# LCD16x2.net
KiCad netlist of a schematic drawn in Altium Designer
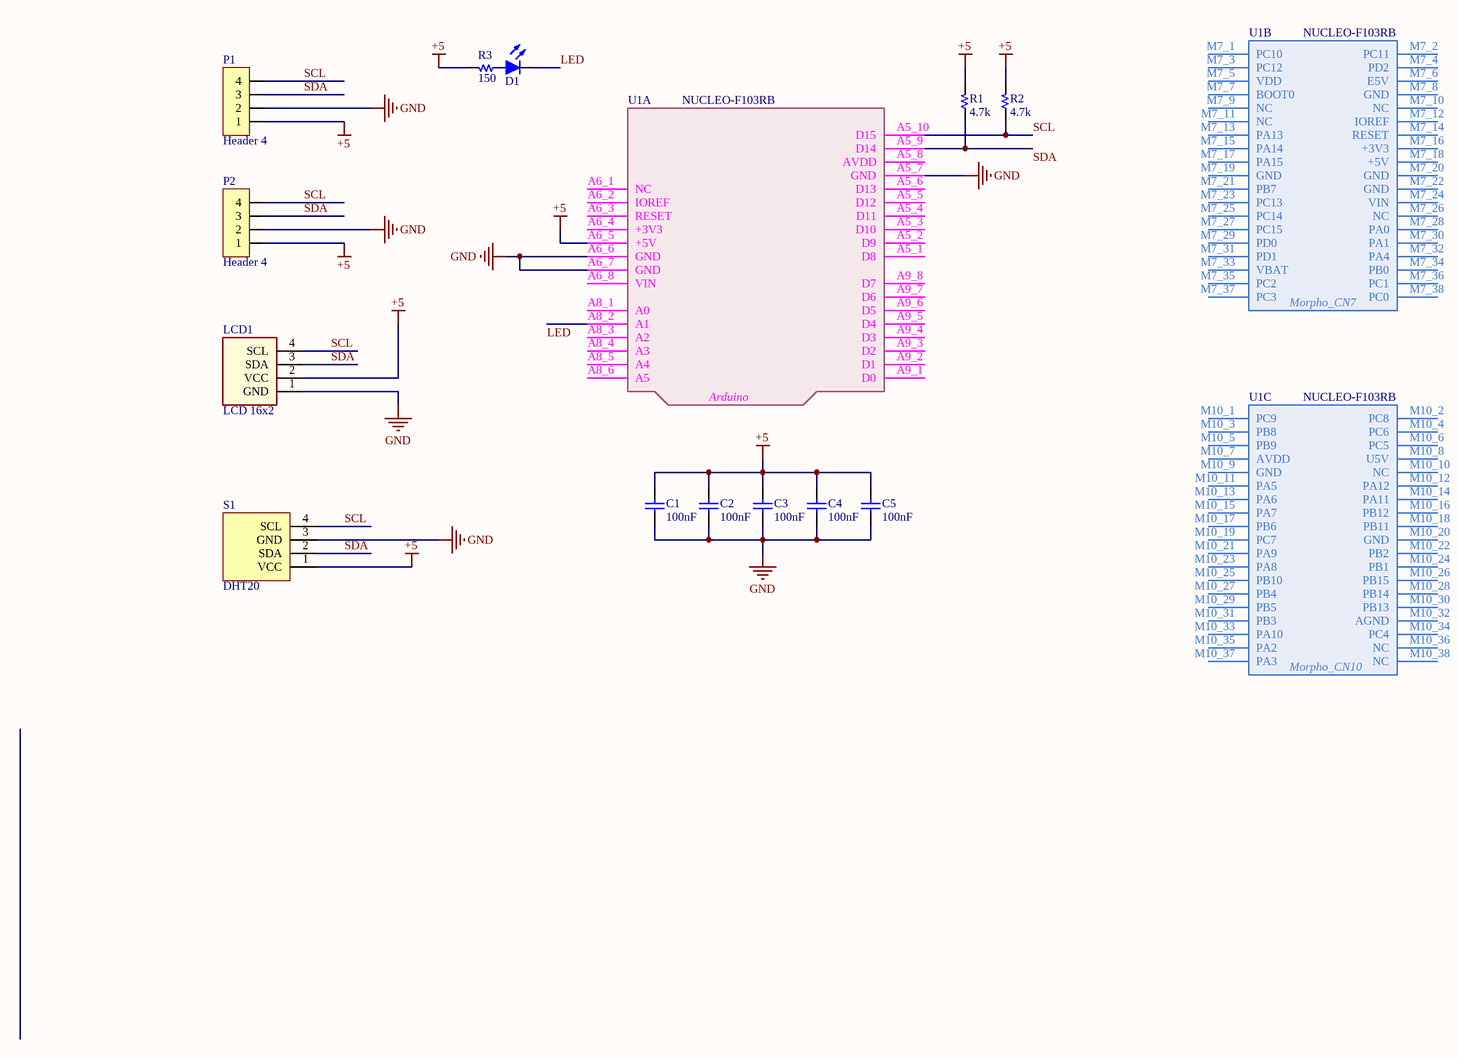
[diagram p0: LCD16x2.SchDoc]

(export (version "E")
  (design (tool "Eeschema 10.0.6"))
  (components
    (comp (ref "C1")
      (value "100nF")
      (footprint "C 0805")
      (description "Capacitor non-pol")
      (libsource (lib "chipfc_altium_libs") (part "Capacitor NP"))
    )
    (comp (ref "C2")
      (value "100nF")
      (footprint "C 0805")
      (description "Capacitor non-pol")
      (libsource (lib "chipfc_altium_libs") (part "Capacitor NP"))
    )
    (comp (ref "C3")
      (value "100nF")
      (footprint "C 0805")
      (description "Capacitor non-pol")
      (libsource (lib "chipfc_altium_libs") (part "Capacitor NP"))
    )
    (comp (ref "C4")
      (value "100nF")
      (footprint "C 0805")
      (description "Capacitor non-pol")
      (libsource (lib "chipfc_altium_libs") (part "Capacitor NP"))
    )
    (comp (ref "C5")
      (value "100nF")
      (footprint "C 0805")
      (description "Capacitor non-pol")
      (libsource (lib "chipfc_altium_libs") (part "Capacitor NP"))
    )
    (comp (ref "D1")
      (value "Led")
      (footprint "LED 3MM - red")
      (description "Typical LED")
      (libsource (lib "chipfc_altium_libs") (part "Led"))
    )
    (comp (ref "LCD1")
      (value "LCD 16x2")
      (footprint "LCD 1602A I2C")
      (description "Character LCD 16x2")
      (libsource (lib "bk2022") (part "LCD 16x2"))
    )
    (comp (ref "P1")
      (value "Header 4")
      (footprint "HDR/Header/4/BOX")
      (description "Header, 4-Pin")
      (libsource (lib "chipfc_altium_libs") (part "Header 4"))
    )
    (comp (ref "P2")
      (value "Header 4")
      (footprint "HDR/Header/4/BOX")
      (description "Header, 4-Pin")
      (libsource (lib "chipfc_altium_libs") (part "Header 4"))
    )
    (comp (ref "R1")
      (value "4.7k")
      (footprint "R 0805")
      (description "Resistor")
      (libsource (lib "chipfc_altium_libs") (part "Resistor"))
    )
    (comp (ref "R2")
      (value "4.7k")
      (footprint "R 0805")
      (description "Resistor")
      (libsource (lib "chipfc_altium_libs") (part "Resistor"))
    )
    (comp (ref "R3")
      (value "150")
      (footprint "R 0805")
      (description "Resistor")
      (libsource (lib "chipfc_altium_libs") (part "Resistor"))
    )
    (comp (ref "S1")
      (value "DHT20")
      (footprint "DTH20/H")
      (description "DTH20 Temperature and humidity module")
      (libsource (lib "chipfc_altium_libs") (part "DTH20"))
    )
    (comp (ref "U1")
      (value "NUCLEO-F103RB")
      (footprint "NUCLEO")
      (fields (field (name "MANUFACTURER") "STMicroelectronics"))
      (libsource (lib "nucleo") (part "NUCLEO-F103RB"))
    )
  )
  (nets
    (net (code "1") (name "+5") (class "Default")
      (node (ref "C1") (pin "1") (pinfunction "1_1") (pintype "passive"))
      (node (ref "C2") (pin "1") (pinfunction "1_1") (pintype "passive"))
      (node (ref "C3") (pin "1") (pinfunction "1_1") (pintype "passive"))
      (node (ref "C4") (pin "1") (pinfunction "1_1") (pintype "passive"))
      (node (ref "C5") (pin "1") (pinfunction "1_1") (pintype "passive"))
      (node (ref "LCD1") (pin "2") (pinfunction "VCC_2") (pintype "passive"))
      (node (ref "P1") (pin "1") (pinfunction "1_1") (pintype "passive"))
      (node (ref "P2") (pin "1") (pinfunction "1_1") (pintype "passive"))
      (node (ref "R1") (pin "2") (pinfunction "2_2") (pintype "passive"))
      (node (ref "R2") (pin "2") (pinfunction "2_2") (pintype "passive"))
      (node (ref "R3") (pin "2") (pinfunction "2_2") (pintype "passive"))
      (node (ref "S1") (pin "1") (pinfunction "VCC_1") (pintype "passive"))
      (node (ref "U1") (pin "A6_5") (pinfunction "+5V_A6_5") (pintype "passive"))
    )
    (net (code "2") (name "/LED") (class "Default")
      (node (ref "D1") (pin "2") (pinfunction "K_2") (pintype "passive"))
      (node (ref "U1") (pin "A8_2") (pinfunction "A1_A8_2") (pintype "passive"))
    )
    (net (code "3") (name "/SCL") (class "Default")
      (node (ref "LCD1") (pin "4") (pinfunction "SCL_4") (pintype "passive"))
      (node (ref "P1") (pin "4") (pinfunction "4_4") (pintype "passive"))
      (node (ref "P2") (pin "4") (pinfunction "4_4") (pintype "passive"))
      (node (ref "R2") (pin "1") (pinfunction "1_1") (pintype "passive"))
      (node (ref "S1") (pin "4") (pinfunction "SCL_4") (pintype "passive"))
      (node (ref "U1") (pin "A5_10") (pinfunction "D15_A5_10") (pintype "passive"))
    )
    (net (code "4") (name "/SDA") (class "Default")
      (node (ref "LCD1") (pin "3") (pinfunction "SDA_3") (pintype "passive"))
      (node (ref "P1") (pin "3") (pinfunction "3_3") (pintype "passive"))
      (node (ref "P2") (pin "3") (pinfunction "3_3") (pintype "passive"))
      (node (ref "R1") (pin "1") (pinfunction "1_1") (pintype "passive"))
      (node (ref "S1") (pin "2") (pinfunction "SDA_2") (pintype "passive"))
      (node (ref "U1") (pin "A5_9") (pinfunction "D14_A5_9") (pintype "passive"))
    )
    (net (code "5") (name "GND") (class "Default")
      (node (ref "C1") (pin "2") (pinfunction "2_2") (pintype "passive"))
      (node (ref "C2") (pin "2") (pinfunction "2_2") (pintype "passive"))
      (node (ref "C3") (pin "2") (pinfunction "2_2") (pintype "passive"))
      (node (ref "C4") (pin "2") (pinfunction "2_2") (pintype "passive"))
      (node (ref "C5") (pin "2") (pinfunction "2_2") (pintype "passive"))
      (node (ref "LCD1") (pin "1") (pinfunction "GND_1") (pintype "passive"))
      (node (ref "P1") (pin "2") (pinfunction "2_2") (pintype "passive"))
      (node (ref "P2") (pin "2") (pinfunction "2_2") (pintype "passive"))
      (node (ref "S1") (pin "3") (pinfunction "GND_3") (pintype "passive"))
      (node (ref "U1") (pin "A5_7") (pinfunction "GND_A5_7") (pintype "passive"))
      (node (ref "U1") (pin "A6_6") (pinfunction "GND_A6_6") (pintype "passive"))
      (node (ref "U1") (pin "A6_7") (pinfunction "GND_A6_7") (pintype "passive"))
    )
    (net (code "6") (name "Net-(D1-A)") (class "Default")
      (node (ref "D1") (pin "1") (pinfunction "A_1") (pintype "passive"))
      (node (ref "R3") (pin "1") (pinfunction "1_1") (pintype "passive"))
    )
    (net (code "7") (name "unconnected-(U1A-+3V3-PadA6_4)") (class "Default")
      (node (ref "U1") (pin "A6_4") (pinfunction "+3V3_A6_4") (pintype "passive"))
    )
    (net (code "8") (name "unconnected-(U1A-A0-PadA8_1)") (class "Default")
      (node (ref "U1") (pin "A8_1") (pinfunction "A0_A8_1") (pintype "passive"))
    )
    (net (code "9") (name "unconnected-(U1A-A2-PadA8_3)") (class "Default")
      (node (ref "U1") (pin "A8_3") (pinfunction "A2_A8_3") (pintype "passive"))
    )
    (net (code "10") (name "unconnected-(U1A-A3-PadA8_4)") (class "Default")
      (node (ref "U1") (pin "A8_4") (pinfunction "A3_A8_4") (pintype "passive"))
    )
    (net (code "11") (name "unconnected-(U1A-A4-PadA8_5)") (class "Default")
      (node (ref "U1") (pin "A8_5") (pinfunction "A4_A8_5") (pintype "passive"))
    )
    (net (code "12") (name "unconnected-(U1A-A5-PadA8_6)") (class "Default")
      (node (ref "U1") (pin "A8_6") (pinfunction "A5_A8_6") (pintype "passive"))
    )
    (net (code "13") (name "unconnected-(U1A-AVDD-PadA5_8)") (class "Default")
      (node (ref "U1") (pin "A5_8") (pinfunction "AVDD_A5_8") (pintype "passive"))
    )
    (net (code "14") (name "unconnected-(U1A-D0-PadA9_1)") (class "Default")
      (node (ref "U1") (pin "A9_1") (pinfunction "D0_A9_1") (pintype "passive"))
    )
    (net (code "15") (name "unconnected-(U1A-D1-PadA9_2)") (class "Default")
      (node (ref "U1") (pin "A9_2") (pinfunction "D1_A9_2") (pintype "passive"))
    )
    (net (code "16") (name "unconnected-(U1A-D2-PadA9_3)") (class "Default")
      (node (ref "U1") (pin "A9_3") (pinfunction "D2_A9_3") (pintype "passive"))
    )
    (net (code "17") (name "unconnected-(U1A-D3-PadA9_4)") (class "Default")
      (node (ref "U1") (pin "A9_4") (pinfunction "D3_A9_4") (pintype "passive"))
    )
    (net (code "18") (name "unconnected-(U1A-D4-PadA9_5)") (class "Default")
      (node (ref "U1") (pin "A9_5") (pinfunction "D4_A9_5") (pintype "passive"))
    )
    (net (code "19") (name "unconnected-(U1A-D5-PadA9_6)") (class "Default")
      (node (ref "U1") (pin "A9_6") (pinfunction "D5_A9_6") (pintype "passive"))
    )
    (net (code "20") (name "unconnected-(U1A-D6-PadA9_7)") (class "Default")
      (node (ref "U1") (pin "A9_7") (pinfunction "D6_A9_7") (pintype "passive"))
    )
    (net (code "21") (name "unconnected-(U1A-D7-PadA9_8)") (class "Default")
      (node (ref "U1") (pin "A9_8") (pinfunction "D7_A9_8") (pintype "passive"))
    )
    (net (code "22") (name "unconnected-(U1A-D8-PadA5_1)") (class "Default")
      (node (ref "U1") (pin "A5_1") (pinfunction "D8_A5_1") (pintype "passive"))
    )
    (net (code "23") (name "unconnected-(U1A-D9-PadA5_2)") (class "Default")
      (node (ref "U1") (pin "A5_2") (pinfunction "D9_A5_2") (pintype "passive"))
    )
    (net (code "24") (name "unconnected-(U1A-D10-PadA5_3)") (class "Default")
      (node (ref "U1") (pin "A5_3") (pinfunction "D10_A5_3") (pintype "passive"))
    )
    (net (code "25") (name "unconnected-(U1A-D11-PadA5_4)") (class "Default")
      (node (ref "U1") (pin "A5_4") (pinfunction "D11_A5_4") (pintype "passive"))
    )
    (net (code "26") (name "unconnected-(U1A-D12-PadA5_5)") (class "Default")
      (node (ref "U1") (pin "A5_5") (pinfunction "D12_A5_5") (pintype "passive"))
    )
    (net (code "27") (name "unconnected-(U1A-D13-PadA5_6)") (class "Default")
      (node (ref "U1") (pin "A5_6") (pinfunction "D13_A5_6") (pintype "passive"))
    )
    (net (code "28") (name "unconnected-(U1A-IOREF-PadA6_2)") (class "Default")
      (node (ref "U1") (pin "A6_2") (pinfunction "IOREF_A6_2") (pintype "passive"))
    )
    (net (code "29") (name "unconnected-(U1A-NC-PadA6_1)") (class "Default")
      (node (ref "U1") (pin "A6_1") (pinfunction "NC_A6_1") (pintype "passive"))
    )
    (net (code "30") (name "unconnected-(U1A-RESET-PadA6_3)") (class "Default")
      (node (ref "U1") (pin "A6_3") (pinfunction "RESET_A6_3") (pintype "passive"))
    )
    (net (code "31") (name "unconnected-(U1A-VIN-PadA6_8)") (class "Default")
      (node (ref "U1") (pin "A6_8") (pinfunction "VIN_A6_8") (pintype "passive"))
    )
    (net (code "32") (name "unconnected-(U1B-+3V3-PadM7_16)") (class "Default")
      (node (ref "U1") (pin "M7_16") (pinfunction "+3V3_M7_16") (pintype "passive"))
    )
    (net (code "33") (name "unconnected-(U1B-+5V-PadM7_18)") (class "Default")
      (node (ref "U1") (pin "M7_18") (pinfunction "+5V_M7_18") (pintype "passive"))
    )
    (net (code "34") (name "unconnected-(U1B-BOOT0-PadM7_7)") (class "Default")
      (node (ref "U1") (pin "M7_7") (pinfunction "BOOT0_M7_7") (pintype "passive"))
    )
    (net (code "35") (name "unconnected-(U1B-E5V-PadM7_6)") (class "Default")
      (node (ref "U1") (pin "M7_6") (pinfunction "E5V_M7_6") (pintype "passive"))
    )
    (net (code "36") (name "unconnected-(U1B-GND-PadM7_8)") (class "Default")
      (node (ref "U1") (pin "M7_8") (pinfunction "GND_M7_8") (pintype "passive"))
    )
    (net (code "37") (name "unconnected-(U1B-GND-PadM7_19)") (class "Default")
      (node (ref "U1") (pin "M7_19") (pinfunction "GND_M7_19") (pintype "passive"))
    )
    (net (code "38") (name "unconnected-(U1B-GND-PadM7_20)") (class "Default")
      (node (ref "U1") (pin "M7_20") (pinfunction "GND_M7_20") (pintype "passive"))
    )
    (net (code "39") (name "unconnected-(U1B-GND-PadM7_22)") (class "Default")
      (node (ref "U1") (pin "M7_22") (pinfunction "GND_M7_22") (pintype "passive"))
    )
    (net (code "40") (name "unconnected-(U1B-IOREF-PadM7_12)") (class "Default")
      (node (ref "U1") (pin "M7_12") (pinfunction "IOREF_M7_12") (pintype "passive"))
    )
    (net (code "41") (name "unconnected-(U1B-NC-PadM7_9)") (class "Default")
      (node (ref "U1") (pin "M7_9") (pinfunction "NC_M7_9") (pintype "passive"))
    )
    (net (code "42") (name "unconnected-(U1B-NC-PadM7_10)") (class "Default")
      (node (ref "U1") (pin "M7_10") (pinfunction "NC_M7_10") (pintype "passive"))
    )
    (net (code "43") (name "unconnected-(U1B-NC-PadM7_11)") (class "Default")
      (node (ref "U1") (pin "M7_11") (pinfunction "NC_M7_11") (pintype "passive"))
    )
    (net (code "44") (name "unconnected-(U1B-NC-PadM7_26)") (class "Default")
      (node (ref "U1") (pin "M7_26") (pinfunction "NC_M7_26") (pintype "passive"))
    )
    (net (code "45") (name "unconnected-(U1B-PA0-PadM7_28)") (class "Default")
      (node (ref "U1") (pin "M7_28") (pinfunction "PA0_M7_28") (pintype "passive"))
    )
    (net (code "46") (name "unconnected-(U1B-PA1-PadM7_30)") (class "Default")
      (node (ref "U1") (pin "M7_30") (pinfunction "PA1_M7_30") (pintype "passive"))
    )
    (net (code "47") (name "unconnected-(U1B-PA4-PadM7_32)") (class "Default")
      (node (ref "U1") (pin "M7_32") (pinfunction "PA4_M7_32") (pintype "passive"))
    )
    (net (code "48") (name "unconnected-(U1B-PA13-PadM7_13)") (class "Default")
      (node (ref "U1") (pin "M7_13") (pinfunction "PA13_M7_13") (pintype "passive"))
    )
    (net (code "49") (name "unconnected-(U1B-PA14-PadM7_15)") (class "Default")
      (node (ref "U1") (pin "M7_15") (pinfunction "PA14_M7_15") (pintype "passive"))
    )
    (net (code "50") (name "unconnected-(U1B-PA15-PadM7_17)") (class "Default")
      (node (ref "U1") (pin "M7_17") (pinfunction "PA15_M7_17") (pintype "passive"))
    )
    (net (code "51") (name "unconnected-(U1B-PB0-PadM7_34)") (class "Default")
      (node (ref "U1") (pin "M7_34") (pinfunction "PB0_M7_34") (pintype "passive"))
    )
    (net (code "52") (name "unconnected-(U1B-PB7-PadM7_21)") (class "Default")
      (node (ref "U1") (pin "M7_21") (pinfunction "PB7_M7_21") (pintype "passive"))
    )
    (net (code "53") (name "unconnected-(U1B-PC0-PadM7_38)") (class "Default")
      (node (ref "U1") (pin "M7_38") (pinfunction "PC0_M7_38") (pintype "passive"))
    )
    (net (code "54") (name "unconnected-(U1B-PC1-PadM7_36)") (class "Default")
      (node (ref "U1") (pin "M7_36") (pinfunction "PC1_M7_36") (pintype "passive"))
    )
    (net (code "55") (name "unconnected-(U1B-PC2-PadM7_35)") (class "Default")
      (node (ref "U1") (pin "M7_35") (pinfunction "PC2_M7_35") (pintype "passive"))
    )
    (net (code "56") (name "unconnected-(U1B-PC3-PadM7_37)") (class "Default")
      (node (ref "U1") (pin "M7_37") (pinfunction "PC3_M7_37") (pintype "passive"))
    )
    (net (code "57") (name "unconnected-(U1B-PC10-PadM7_1)") (class "Default")
      (node (ref "U1") (pin "M7_1") (pinfunction "PC10_M7_1") (pintype "passive"))
    )
    (net (code "58") (name "unconnected-(U1B-PC11-PadM7_2)") (class "Default")
      (node (ref "U1") (pin "M7_2") (pinfunction "PC11_M7_2") (pintype "passive"))
    )
    (net (code "59") (name "unconnected-(U1B-PC12-PadM7_3)") (class "Default")
      (node (ref "U1") (pin "M7_3") (pinfunction "PC12_M7_3") (pintype "passive"))
    )
    (net (code "60") (name "unconnected-(U1B-PC13-PadM7_23)") (class "Default")
      (node (ref "U1") (pin "M7_23") (pinfunction "PC13_M7_23") (pintype "passive"))
    )
    (net (code "61") (name "unconnected-(U1B-PC14-PadM7_25)") (class "Default")
      (node (ref "U1") (pin "M7_25") (pinfunction "PC14_M7_25") (pintype "passive"))
    )
    (net (code "62") (name "unconnected-(U1B-PC15-PadM7_27)") (class "Default")
      (node (ref "U1") (pin "M7_27") (pinfunction "PC15_M7_27") (pintype "passive"))
    )
    (net (code "63") (name "unconnected-(U1B-PD0-PadM7_29)") (class "Default")
      (node (ref "U1") (pin "M7_29") (pinfunction "PD0_M7_29") (pintype "passive"))
    )
    (net (code "64") (name "unconnected-(U1B-PD1-PadM7_31)") (class "Default")
      (node (ref "U1") (pin "M7_31") (pinfunction "PD1_M7_31") (pintype "passive"))
    )
    (net (code "65") (name "unconnected-(U1B-PD2-PadM7_4)") (class "Default")
      (node (ref "U1") (pin "M7_4") (pinfunction "PD2_M7_4") (pintype "passive"))
    )
    (net (code "66") (name "unconnected-(U1B-RESET-PadM7_14)") (class "Default")
      (node (ref "U1") (pin "M7_14") (pinfunction "RESET_M7_14") (pintype "passive"))
    )
    (net (code "67") (name "unconnected-(U1B-VBAT-PadM7_33)") (class "Default")
      (node (ref "U1") (pin "M7_33") (pinfunction "VBAT_M7_33") (pintype "passive"))
    )
    (net (code "68") (name "unconnected-(U1B-VDD-PadM7_5)") (class "Default")
      (node (ref "U1") (pin "M7_5") (pinfunction "VDD_M7_5") (pintype "passive"))
    )
    (net (code "69") (name "unconnected-(U1B-VIN-PadM7_24)") (class "Default")
      (node (ref "U1") (pin "M7_24") (pinfunction "VIN_M7_24") (pintype "passive"))
    )
    (net (code "70") (name "unconnected-(U1C-AGND-PadM10_32)") (class "Default")
      (node (ref "U1") (pin "M10_32") (pinfunction "AGND_M10_32") (pintype "passive"))
    )
    (net (code "71") (name "unconnected-(U1C-AVDD-PadM10_7)") (class "Default")
      (node (ref "U1") (pin "M10_7") (pinfunction "AVDD_M10_7") (pintype "passive"))
    )
    (net (code "72") (name "unconnected-(U1C-GND-PadM10_9)") (class "Default")
      (node (ref "U1") (pin "M10_9") (pinfunction "GND_M10_9") (pintype "passive"))
    )
    (net (code "73") (name "unconnected-(U1C-GND-PadM10_20)") (class "Default")
      (node (ref "U1") (pin "M10_20") (pinfunction "GND_M10_20") (pintype "passive"))
    )
    (net (code "74") (name "unconnected-(U1C-NC-PadM10_10)") (class "Default")
      (node (ref "U1") (pin "M10_10") (pinfunction "NC_M10_10") (pintype "passive"))
    )
    (net (code "75") (name "unconnected-(U1C-NC-PadM10_36)") (class "Default")
      (node (ref "U1") (pin "M10_36") (pinfunction "NC_M10_36") (pintype "passive"))
    )
    (net (code "76") (name "unconnected-(U1C-NC-PadM10_38)") (class "Default")
      (node (ref "U1") (pin "M10_38") (pinfunction "NC_M10_38") (pintype "passive"))
    )
    (net (code "77") (name "unconnected-(U1C-PA2-PadM10_35)") (class "Default")
      (node (ref "U1") (pin "M10_35") (pinfunction "PA2_M10_35") (pintype "passive"))
    )
    (net (code "78") (name "unconnected-(U1C-PA3-PadM10_37)") (class "Default")
      (node (ref "U1") (pin "M10_37") (pinfunction "PA3_M10_37") (pintype "passive"))
    )
    (net (code "79") (name "unconnected-(U1C-PA5-PadM10_11)") (class "Default")
      (node (ref "U1") (pin "M10_11") (pinfunction "PA5_M10_11") (pintype "passive"))
    )
    (net (code "80") (name "unconnected-(U1C-PA6-PadM10_13)") (class "Default")
      (node (ref "U1") (pin "M10_13") (pinfunction "PA6_M10_13") (pintype "passive"))
    )
    (net (code "81") (name "unconnected-(U1C-PA7-PadM10_15)") (class "Default")
      (node (ref "U1") (pin "M10_15") (pinfunction "PA7_M10_15") (pintype "passive"))
    )
    (net (code "82") (name "unconnected-(U1C-PA8-PadM10_23)") (class "Default")
      (node (ref "U1") (pin "M10_23") (pinfunction "PA8_M10_23") (pintype "passive"))
    )
    (net (code "83") (name "unconnected-(U1C-PA9-PadM10_21)") (class "Default")
      (node (ref "U1") (pin "M10_21") (pinfunction "PA9_M10_21") (pintype "passive"))
    )
    (net (code "84") (name "unconnected-(U1C-PA10-PadM10_33)") (class "Default")
      (node (ref "U1") (pin "M10_33") (pinfunction "PA10_M10_33") (pintype "passive"))
    )
    (net (code "85") (name "unconnected-(U1C-PA11-PadM10_14)") (class "Default")
      (node (ref "U1") (pin "M10_14") (pinfunction "PA11_M10_14") (pintype "passive"))
    )
    (net (code "86") (name "unconnected-(U1C-PA12-PadM10_12)") (class "Default")
      (node (ref "U1") (pin "M10_12") (pinfunction "PA12_M10_12") (pintype "passive"))
    )
    (net (code "87") (name "unconnected-(U1C-PB1-PadM10_24)") (class "Default")
      (node (ref "U1") (pin "M10_24") (pinfunction "PB1_M10_24") (pintype "passive"))
    )
    (net (code "88") (name "unconnected-(U1C-PB2-PadM10_22)") (class "Default")
      (node (ref "U1") (pin "M10_22") (pinfunction "PB2_M10_22") (pintype "passive"))
    )
    (net (code "89") (name "unconnected-(U1C-PB3-PadM10_31)") (class "Default")
      (node (ref "U1") (pin "M10_31") (pinfunction "PB3_M10_31") (pintype "passive"))
    )
    (net (code "90") (name "unconnected-(U1C-PB4-PadM10_27)") (class "Default")
      (node (ref "U1") (pin "M10_27") (pinfunction "PB4_M10_27") (pintype "passive"))
    )
    (net (code "91") (name "unconnected-(U1C-PB5-PadM10_29)") (class "Default")
      (node (ref "U1") (pin "M10_29") (pinfunction "PB5_M10_29") (pintype "passive"))
    )
    (net (code "92") (name "unconnected-(U1C-PB6-PadM10_17)") (class "Default")
      (node (ref "U1") (pin "M10_17") (pinfunction "PB6_M10_17") (pintype "passive"))
    )
    (net (code "93") (name "unconnected-(U1C-PB8-PadM10_3)") (class "Default")
      (node (ref "U1") (pin "M10_3") (pinfunction "PB8_M10_3") (pintype "passive"))
    )
    (net (code "94") (name "unconnected-(U1C-PB9-PadM10_5)") (class "Default")
      (node (ref "U1") (pin "M10_5") (pinfunction "PB9_M10_5") (pintype "passive"))
    )
    (net (code "95") (name "unconnected-(U1C-PB10-PadM10_25)") (class "Default")
      (node (ref "U1") (pin "M10_25") (pinfunction "PB10_M10_25") (pintype "passive"))
    )
    (net (code "96") (name "unconnected-(U1C-PB11-PadM10_18)") (class "Default")
      (node (ref "U1") (pin "M10_18") (pinfunction "PB11_M10_18") (pintype "passive"))
    )
    (net (code "97") (name "unconnected-(U1C-PB12-PadM10_16)") (class "Default")
      (node (ref "U1") (pin "M10_16") (pinfunction "PB12_M10_16") (pintype "passive"))
    )
    (net (code "98") (name "unconnected-(U1C-PB13-PadM10_30)") (class "Default")
      (node (ref "U1") (pin "M10_30") (pinfunction "PB13_M10_30") (pintype "passive"))
    )
    (net (code "99") (name "unconnected-(U1C-PB14-PadM10_28)") (class "Default")
      (node (ref "U1") (pin "M10_28") (pinfunction "PB14_M10_28") (pintype "passive"))
    )
    (net (code "100") (name "unconnected-(U1C-PB15-PadM10_26)") (class "Default")
      (node (ref "U1") (pin "M10_26") (pinfunction "PB15_M10_26") (pintype "passive"))
    )
    (net (code "101") (name "unconnected-(U1C-PC4-PadM10_34)") (class "Default")
      (node (ref "U1") (pin "M10_34") (pinfunction "PC4_M10_34") (pintype "passive"))
    )
    (net (code "102") (name "unconnected-(U1C-PC5-PadM10_6)") (class "Default")
      (node (ref "U1") (pin "M10_6") (pinfunction "PC5_M10_6") (pintype "passive"))
    )
    (net (code "103") (name "unconnected-(U1C-PC6-PadM10_4)") (class "Default")
      (node (ref "U1") (pin "M10_4") (pinfunction "PC6_M10_4") (pintype "passive"))
    )
    (net (code "104") (name "unconnected-(U1C-PC7-PadM10_19)") (class "Default")
      (node (ref "U1") (pin "M10_19") (pinfunction "PC7_M10_19") (pintype "passive"))
    )
    (net (code "105") (name "unconnected-(U1C-PC8-PadM10_2)") (class "Default")
      (node (ref "U1") (pin "M10_2") (pinfunction "PC8_M10_2") (pintype "passive"))
    )
    (net (code "106") (name "unconnected-(U1C-PC9-PadM10_1)") (class "Default")
      (node (ref "U1") (pin "M10_1") (pinfunction "PC9_M10_1") (pintype "passive"))
    )
    (net (code "107") (name "unconnected-(U1C-U5V-PadM10_8)") (class "Default")
      (node (ref "U1") (pin "M10_8") (pinfunction "U5V_M10_8") (pintype "passive"))
    )
  )
)
